# Power.net
KiCad netlist of a schematic drawn in Altium Designer
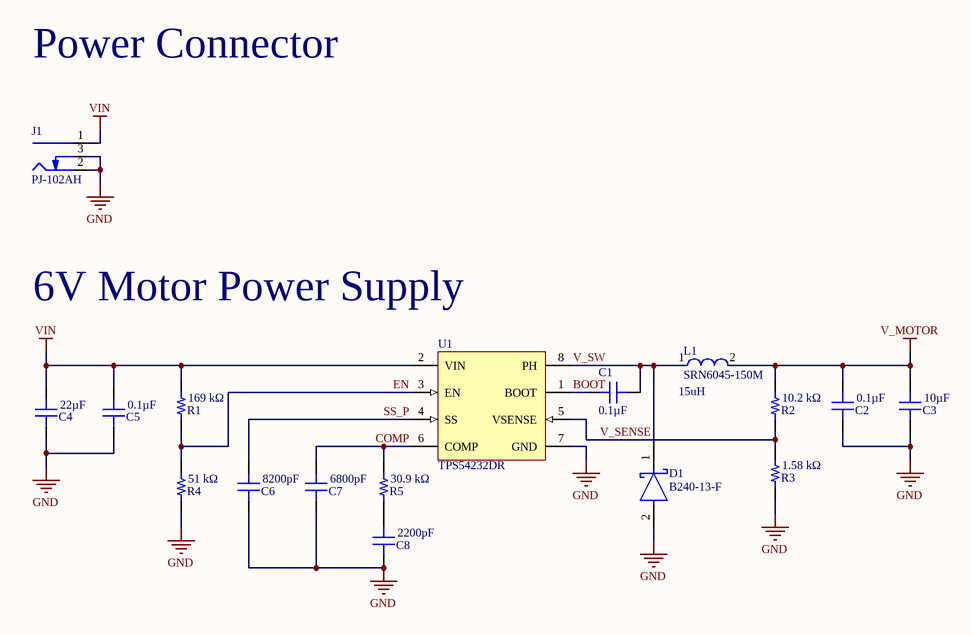
[diagram p0: Power.SchDoc]

(export (version "E")
  (design (tool "Eeschema 10.0.6"))
  (components
    (comp (ref "C1")
      (value "0.1µF")
      (footprint "CAP 0603_1608")
      (description "CAP CER 0.1UF 25V X7R 0603")
      (fields (field (name "PART NUMBER") "06033C104JAT2A") (field (name "MANUFACTURER") "AVX Corporation"))
      (libsource (lib "Generic Altium Database") (part "Capacitor"))
    )
    (comp (ref "C2")
      (value "0.1µF")
      (footprint "CAP 0603_1608")
      (description "CAP CER 0.1UF 25V X7R 0603")
      (fields (field (name "PART NUMBER") "06033C104JAT2A") (field (name "MANUFACTURER") "AVX Corporation"))
      (libsource (lib "Generic Altium Database") (part "Capacitor"))
    )
    (comp (ref "C3")
      (value "10µF")
      (footprint "CAP 0805_2012")
      (description "CAP CER 10UF 25V X5R 0805")
      (fields (field (name "PART NUMBER") "08053D106KAT2A") (field (name "MANUFACTURER") "AVX Corporation"))
      (libsource (lib "Generic Altium Database") (part "Capacitor"))
    )
    (comp (ref "C4")
      (value "22µF")
      (footprint "CAP 0805_2012")
      (description "CAP CER 22UF 25V X5R 0805")
      (fields
        (field (name "PART NUMBER") "C2012X5R1E226M125AC")
        (field (name "MANUFACTURER") "TDK Corporation")
      )
      (libsource (lib "Generic Altium Database") (part "Capacitor"))
    )
    (comp (ref "C5")
      (value "0.1µF")
      (footprint "CAP 0603_1608")
      (description "CAP CER 0.1UF 25V X7R 0603")
      (fields (field (name "PART NUMBER") "06033C104JAT2A") (field (name "MANUFACTURER") "AVX Corporation"))
      (libsource (lib "Generic Altium Database") (part "Capacitor"))
    )
    (comp (ref "C6")
      (value "8200pF")
      (footprint "CAP 0603_1608")
      (description "CAP CER 8200PF 50V X7R 0603")
      (fields (field (name "PART NUMBER") "06035C822KAT2A") (field (name "MANUFACTURER") "AVX Corporation"))
      (libsource (lib "Generic Altium Database") (part "Capacitor"))
    )
    (comp (ref "C7")
      (value "6800pF")
      (footprint "CAP 0603_1608")
      (description "CAP CER 6800PF 25V X7R 0603")
      (fields (field (name "PART NUMBER") "06033C682JAT2A") (field (name "MANUFACTURER") "AVX Corporation"))
      (libsource (lib "Generic Altium Database") (part "Capacitor"))
    )
    (comp (ref "C8")
      (value "2200pF")
      (footprint "CAP 0603_1608")
      (description "CAP CER 2200PF 25V X7R 0603")
      (fields (field (name "PART NUMBER") "06033C222JAT2A") (field (name "MANUFACTURER") "AVX Corporation"))
      (libsource (lib "Generic Altium Database") (part "Capacitor"))
    )
    (comp (ref "D1")
      (value "B240-13-F")
      (footprint "FP-SMB-MFG")
      (description "DIODE SCHOTTKY 40V 2A SMB")
      (fields
        (field (name "MANUFACTURER") "Diodes Inc.")
        (field (name "OCTOPART") "https://octopart.com/b240-13-f-diodes+inc.-325780")
      )
      (libsource (lib "Altium Content Vault") (part "1d6ec82d83fb6aee721767c19dac4b9"))
    )
    (comp (ref "J1")
      (value "PJ-102AH")
      (footprint "CUI PJ-102AH")
      (description "CONN PWR JACK 2X5.5MM SOLDER")
      (fields (field (name "MANUFACTURER") "CUI Devices"))
      (libsource (lib "Generic Altium Database") (part "Barrel Connector"))
    )
    (comp (ref "L1")
      (value "SRN6045-150M")
      (footprint "FP-SRN6045-MFG")
      (description "FIXED IND 15UH 1.9A 95.8MOHM SMD")
      (fields (field (name "INDUCTANCE") "15uH") (field (name "TOLERANCE") "20%"))
      (libsource (lib "Altium Content Vault") (part "725321dda6339637d4d059423bc1c3c"))
    )
    (comp (ref "R1")
      (value "169 kΩ")
      (footprint "RES 0603_1608")
      (description "RES SMD 169K OHM 1% 1/10W 0603")
      (fields (field (name "PART NUMBER") "RC0603FR-07169KL") (field (name "MANUFACTURER") "Yageo"))
      (libsource (lib "Generic Altium Database") (part "Resistor"))
    )
    (comp (ref "R2")
      (value "10.2 kΩ")
      (footprint "RES 0603_1608")
      (description "RES SMD 10.2K OHM 1% 1/10W 0603")
      (fields (field (name "PART NUMBER") "AC0603FR-0710K2L") (field (name "MANUFACTURER") "Yageo"))
      (libsource (lib "Generic Altium Database") (part "Resistor"))
    )
    (comp (ref "R3")
      (value "1.58 kΩ")
      (footprint "RES 0603_1608")
      (description "RES SMD 1.58K OHM 1% 1/10W 0603")
      (fields (field (name "PART NUMBER") "CR0603-FX-1581ELF") (field (name "MANUFACTURER") "Bourns Inc."))
      (libsource (lib "Generic Altium Database") (part "Resistor"))
    )
    (comp (ref "R4")
      (value "51 kΩ")
      (footprint "RES 0603_1608")
      (description "RES SMD 51K OHM 1% 1/10W 0603")
      (fields (field (name "PART NUMBER") "AC0603FR-0751KL") (field (name "MANUFACTURER") "Yageo"))
      (libsource (lib "Generic Altium Database") (part "Resistor"))
    )
    (comp (ref "R5")
      (value "30.9 kΩ")
      (footprint "RES 0603_1608")
      (description "RES SMD 30.9K OHM 1% 1/10W 0603")
      (fields (field (name "PART NUMBER") "CR0603-FX-3092ELF") (field (name "MANUFACTURER") "Bourns Inc."))
      (libsource (lib "Generic Altium Database") (part "Resistor"))
    )
    (comp (ref "U1")
      (value "TPS54232DR")
      (footprint "D0008A_M")
      (fields (field (name "MANUFACTURER") "Texas Instruments"))
      (libsource (lib "Altium Content Vault") (part "TI-TPS54232D8"))
    )
  )
  (nets
    (net (code "1") (name "/BOOT") (class "Default")
      (node (ref "C1") (pin "2") (pinfunction "2_2") (pintype "passive"))
      (node (ref "U1") (pin "1") (pinfunction "BOOT_1") (pintype "passive"))
    )
    (net (code "2") (name "/COMP") (class "Default")
      (node (ref "C7") (pin "2") (pinfunction "2_2") (pintype "passive"))
      (node (ref "R5") (pin "2") (pinfunction "2_2") (pintype "passive"))
      (node (ref "U1") (pin "6") (pinfunction "COMP_6") (pintype "passive"))
    )
    (net (code "3") (name "/EN") (class "Default")
      (node (ref "R1") (pin "1") (pinfunction "1_1") (pintype "passive"))
      (node (ref "R4") (pin "2") (pinfunction "2_2") (pintype "passive"))
      (node (ref "U1") (pin "3") (pinfunction "EN_3") (pintype "input"))
    )
    (net (code "4") (name "/SS_P") (class "Default")
      (node (ref "C6") (pin "2") (pinfunction "2_2") (pintype "passive"))
      (node (ref "U1") (pin "4") (pinfunction "SS_4") (pintype "input"))
    )
    (net (code "5") (name "/V_SENSE") (class "Default")
      (node (ref "R2") (pin "1") (pinfunction "1_1") (pintype "passive"))
      (node (ref "R3") (pin "2") (pinfunction "2_2") (pintype "passive"))
      (node (ref "U1") (pin "5") (pinfunction "VSENSE_5") (pintype "input"))
    )
    (net (code "6") (name "/V_SW") (class "Default")
      (node (ref "C1") (pin "1") (pinfunction "1_1") (pintype "passive"))
      (node (ref "D1") (pin "1") (pinfunction "C_1") (pintype "passive"))
      (node (ref "L1") (pin "1") (pinfunction "1_1") (pintype "passive"))
      (node (ref "U1") (pin "8") (pinfunction "PH_8") (pintype "power_in"))
    )
    (net (code "7") (name "GND") (class "Default")
      (node (ref "C2") (pin "1") (pinfunction "1_1") (pintype "passive"))
      (node (ref "C3") (pin "1") (pinfunction "1_1") (pintype "passive"))
      (node (ref "C4") (pin "1") (pinfunction "1_1") (pintype "passive"))
      (node (ref "C5") (pin "1") (pinfunction "1_1") (pintype "passive"))
      (node (ref "C6") (pin "1") (pinfunction "1_1") (pintype "passive"))
      (node (ref "C7") (pin "1") (pinfunction "1_1") (pintype "passive"))
      (node (ref "C8") (pin "1") (pinfunction "1_1") (pintype "passive"))
      (node (ref "D1") (pin "2") (pinfunction "A_2") (pintype "passive"))
      (node (ref "J1") (pin "2") (pinfunction "Outer_2") (pintype "passive"))
      (node (ref "J1") (pin "3") (pinfunction "SW_3") (pintype "passive"))
      (node (ref "R3") (pin "1") (pinfunction "1_1") (pintype "passive"))
      (node (ref "R4") (pin "1") (pinfunction "1_1") (pintype "passive"))
      (node (ref "U1") (pin "7") (pinfunction "GND_7") (pintype "power_in"))
    )
    (net (code "8") (name "Net-(C8-Pad2)") (class "Default")
      (node (ref "C8") (pin "2") (pinfunction "2_2") (pintype "passive"))
      (node (ref "R5") (pin "1") (pinfunction "1_1") (pintype "passive"))
    )
    (net (code "9") (name "VIN") (class "Default")
      (node (ref "C4") (pin "2") (pinfunction "2_2") (pintype "passive"))
      (node (ref "C5") (pin "2") (pinfunction "2_2") (pintype "passive"))
      (node (ref "J1") (pin "1") (pinfunction "Centre_1") (pintype "passive"))
      (node (ref "R1") (pin "2") (pinfunction "2_2") (pintype "passive"))
      (node (ref "U1") (pin "2") (pinfunction "VIN_2") (pintype "power_in"))
    )
    (net (code "10") (name "V_MOTOR") (class "Default")
      (node (ref "C2") (pin "2") (pinfunction "2_2") (pintype "passive"))
      (node (ref "C3") (pin "2") (pinfunction "2_2") (pintype "passive"))
      (node (ref "L1") (pin "2") (pinfunction "2_2") (pintype "passive"))
      (node (ref "R2") (pin "2") (pinfunction "2_2") (pintype "passive"))
    )
  )
)
